# 1-Schematic_Plan_B_elektronisch_schema_o.net
KiCad netlist of a schematic drawn in EasyEDA
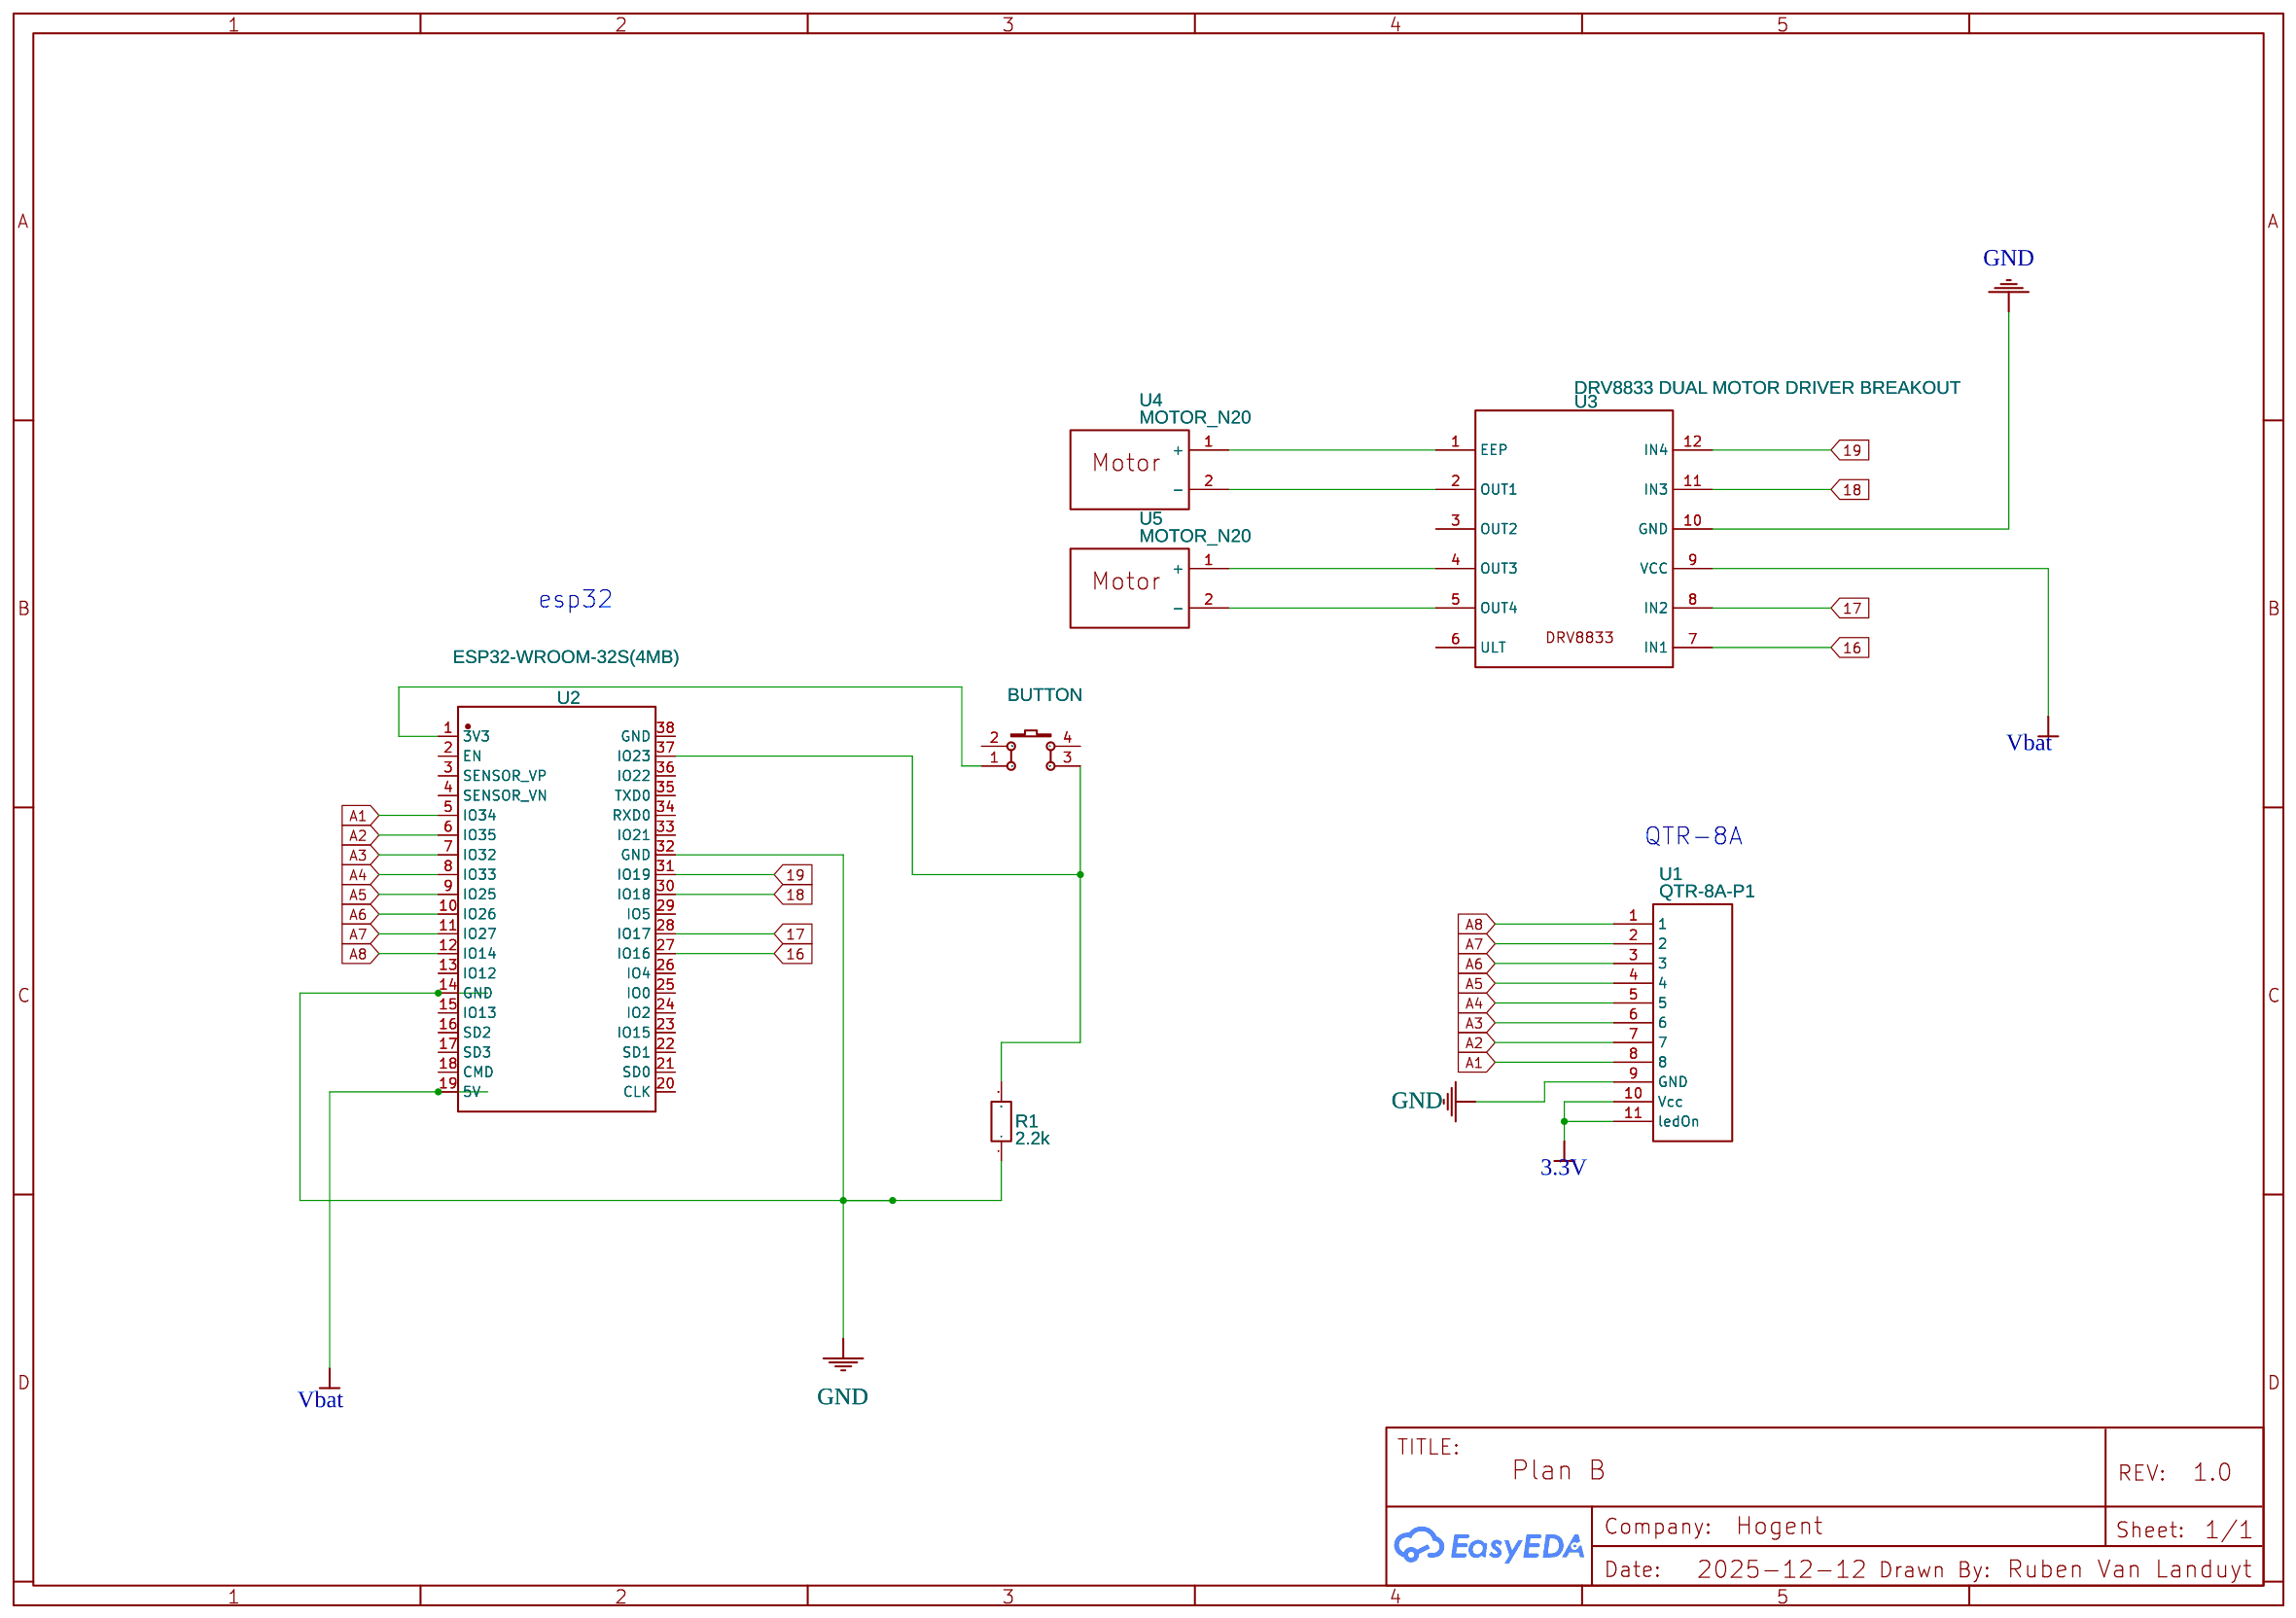
[diagram p0: schematic sheet]

(export (version "E")
  (design (tool "Eeschema 10.0.6"))
  (components
    (comp (ref "BUTTON")
      (value "K4-6×6_SMD")
      (fields (field (name "Manufacturer Part") "K2-6639SP-D4SC-04") (field (name "Manufacturer") "韩国韩荣"))
      (libsource (lib "") (part "K4-6×6_SMD"))
    )
    (comp (ref "R1") (value "2.2k") (libsource (lib "") (part "R_0805_EU")))
    (comp (ref "U1") (value "QTR-8A-P1") (libsource (lib "") (part "QTR-8A-P1")))
    (comp (ref "U2")
      (value "ESP32-WROOM-32S(4MB)")
      (fields (field (name "Manufacturer") "Espressif Systems"))
      (libsource (lib "") (part "ESP32-WROOM-32S(4MB)"))
    )
    (comp (ref "U3")
      (value "DRV8833 DUAL MOTOR DRIVER BREAKOUT")
      (libsource (lib "") (part "DRV8833 DUAL MOTOR DRIVER BREAKOUT"))
    )
    (comp (ref "U4") (value "MOTOR_N20") (libsource (lib "") (part "MOTOR_N20")))
    (comp (ref "U5") (value "MOTOR_N20") (libsource (lib "") (part "MOTOR_N20")))
  )
  (nets
    (net (code "1") (name "3.3V") (class "Default")
      (node (ref "U1") (pin "10") (pinfunction "Vcc_10") (pintype "unspecified"))
      (node (ref "U1") (pin "11") (pinfunction "ledOn_11") (pintype "unspecified"))
    )
    (net (code "2") (name "16") (class "Default")
      (node (ref "U2") (pin "27") (pinfunction "IO16_27") (pintype "unspecified"))
      (node (ref "U3") (pin "7") (pinfunction "IN1_7") (pintype "unspecified"))
    )
    (net (code "3") (name "17") (class "Default")
      (node (ref "U2") (pin "28") (pinfunction "IO17_28") (pintype "unspecified"))
      (node (ref "U3") (pin "8") (pinfunction "IN2_8") (pintype "unspecified"))
    )
    (net (code "4") (name "18") (class "Default")
      (node (ref "U2") (pin "30") (pinfunction "IO18_30") (pintype "unspecified"))
      (node (ref "U3") (pin "11") (pinfunction "IN3_11") (pintype "unspecified"))
    )
    (net (code "5") (name "19") (class "Default")
      (node (ref "U2") (pin "31") (pinfunction "IO19_31") (pintype "unspecified"))
      (node (ref "U3") (pin "12") (pinfunction "IN4_12") (pintype "unspecified"))
    )
    (net (code "6") (name "A1") (class "Default")
      (node (ref "U1") (pin "8") (pinfunction "8_8") (pintype "unspecified"))
      (node (ref "U2") (pin "5") (pinfunction "IO34_5") (pintype "unspecified"))
    )
    (net (code "7") (name "A2") (class "Default")
      (node (ref "U1") (pin "7") (pinfunction "7_7") (pintype "unspecified"))
      (node (ref "U2") (pin "6") (pinfunction "IO35_6") (pintype "unspecified"))
    )
    (net (code "8") (name "A3") (class "Default")
      (node (ref "U1") (pin "6") (pinfunction "6_6") (pintype "unspecified"))
      (node (ref "U2") (pin "7") (pinfunction "IO32_7") (pintype "unspecified"))
    )
    (net (code "9") (name "A4") (class "Default")
      (node (ref "U1") (pin "5") (pinfunction "5_5") (pintype "unspecified"))
      (node (ref "U2") (pin "8") (pinfunction "IO33_8") (pintype "unspecified"))
    )
    (net (code "10") (name "A5") (class "Default")
      (node (ref "U1") (pin "4") (pinfunction "4_4") (pintype "unspecified"))
      (node (ref "U2") (pin "9") (pinfunction "IO25_9") (pintype "unspecified"))
    )
    (net (code "11") (name "A6") (class "Default")
      (node (ref "U1") (pin "3") (pinfunction "3_3") (pintype "unspecified"))
      (node (ref "U2") (pin "10") (pinfunction "IO26_10") (pintype "unspecified"))
    )
    (net (code "12") (name "A7") (class "Default")
      (node (ref "U1") (pin "2") (pinfunction "2_2") (pintype "unspecified"))
      (node (ref "U2") (pin "11") (pinfunction "IO27_11") (pintype "unspecified"))
    )
    (net (code "13") (name "A8") (class "Default")
      (node (ref "U1") (pin "1") (pinfunction "1_1") (pintype "unspecified"))
      (node (ref "U2") (pin "12") (pinfunction "IO14_12") (pintype "unspecified"))
    )
    (net (code "14") (name "GND") (class "Default")
      (node (ref "R1") (pin "1") (pinfunction "1_1") (pintype "unspecified"))
      (node (ref "U1") (pin "9") (pinfunction "GND_9") (pintype "unspecified"))
      (node (ref "U2") (pin "14") (pinfunction "GND_14") (pintype "unspecified"))
      (node (ref "U2") (pin "32") (pinfunction "GND_32") (pintype "unspecified"))
      (node (ref "U3") (pin "10") (pinfunction "GND_10") (pintype "unspecified"))
    )
    (net (code "15") (name "Net-(U2-3V3)") (class "Default")
      (node (ref "BUTTON") (pin "1") (pinfunction "1_1") (pintype "unspecified"))
      (node (ref "U2") (pin "1") (pinfunction "3V3_1") (pintype "unspecified"))
    )
    (net (code "16") (name "Net-(U2-IO23)") (class "Default")
      (node (ref "BUTTON") (pin "3") (pinfunction "3_3") (pintype "unspecified"))
      (node (ref "R1") (pin "2") (pinfunction "2_2") (pintype "unspecified"))
      (node (ref "U2") (pin "37") (pinfunction "IO23_37") (pintype "unspecified"))
    )
    (net (code "17") (name "Net-(U3-EEP)") (class "Default")
      (node (ref "U3") (pin "1") (pinfunction "EEP_1") (pintype "unspecified"))
      (node (ref "U4") (pin "1") (pinfunction "+_1") (pintype "unspecified"))
    )
    (net (code "18") (name "Net-(U3-OUT1)") (class "Default")
      (node (ref "U3") (pin "2") (pinfunction "OUT1_2") (pintype "unspecified"))
      (node (ref "U4") (pin "2") (pinfunction "-_2") (pintype "unspecified"))
    )
    (net (code "19") (name "Net-(U3-OUT3)") (class "Default")
      (node (ref "U3") (pin "4") (pinfunction "OUT3_4") (pintype "unspecified"))
      (node (ref "U5") (pin "1") (pinfunction "+_1") (pintype "unspecified"))
    )
    (net (code "20") (name "Net-(U3-OUT4)") (class "Default")
      (node (ref "U3") (pin "5") (pinfunction "OUT4_5") (pintype "unspecified"))
      (node (ref "U5") (pin "2") (pinfunction "-_2") (pintype "unspecified"))
    )
    (net (code "21") (name "Vbat") (class "Default")
      (node (ref "U2") (pin "19") (pinfunction "5V_19") (pintype "unspecified"))
      (node (ref "U3") (pin "9") (pinfunction "VCC_9") (pintype "unspecified"))
    )
    (net (code "22") (name "unconnected-(BUTTON-Pad2)") (class "Default")
      (node (ref "BUTTON") (pin "2") (pinfunction "2_2") (pintype "unspecified"))
    )
    (net (code "23") (name "unconnected-(BUTTON-Pad4)") (class "Default")
      (node (ref "BUTTON") (pin "4") (pinfunction "4_4") (pintype "unspecified"))
    )
    (net (code "24") (name "unconnected-(U2-CLK-Pad20)") (class "Default")
      (node (ref "U2") (pin "20") (pinfunction "CLK_20") (pintype "unspecified"))
    )
    (net (code "25") (name "unconnected-(U2-CMD-Pad18)") (class "Default")
      (node (ref "U2") (pin "18") (pinfunction "CMD_18") (pintype "unspecified"))
    )
    (net (code "26") (name "unconnected-(U2-EN-Pad2)") (class "Default")
      (node (ref "U2") (pin "2") (pinfunction "EN_2") (pintype "unspecified"))
    )
    (net (code "27") (name "unconnected-(U2-GND-Pad38)") (class "Default")
      (node (ref "U2") (pin "38") (pinfunction "GND_38") (pintype "unspecified"))
    )
    (net (code "28") (name "unconnected-(U2-IO0-Pad25)") (class "Default")
      (node (ref "U2") (pin "25") (pinfunction "IO0_25") (pintype "unspecified"))
    )
    (net (code "29") (name "unconnected-(U2-IO2-Pad24)") (class "Default")
      (node (ref "U2") (pin "24") (pinfunction "IO2_24") (pintype "unspecified"))
    )
    (net (code "30") (name "unconnected-(U2-IO4-Pad26)") (class "Default")
      (node (ref "U2") (pin "26") (pinfunction "IO4_26") (pintype "unspecified"))
    )
    (net (code "31") (name "unconnected-(U2-IO5-Pad29)") (class "Default")
      (node (ref "U2") (pin "29") (pinfunction "IO5_29") (pintype "unspecified"))
    )
    (net (code "32") (name "unconnected-(U2-IO12-Pad13)") (class "Default")
      (node (ref "U2") (pin "13") (pinfunction "IO12_13") (pintype "unspecified"))
    )
    (net (code "33") (name "unconnected-(U2-IO13-Pad15)") (class "Default")
      (node (ref "U2") (pin "15") (pinfunction "IO13_15") (pintype "unspecified"))
    )
    (net (code "34") (name "unconnected-(U2-IO15-Pad23)") (class "Default")
      (node (ref "U2") (pin "23") (pinfunction "IO15_23") (pintype "unspecified"))
    )
    (net (code "35") (name "unconnected-(U2-IO21-Pad33)") (class "Default")
      (node (ref "U2") (pin "33") (pinfunction "IO21_33") (pintype "unspecified"))
    )
    (net (code "36") (name "unconnected-(U2-IO22-Pad36)") (class "Default")
      (node (ref "U2") (pin "36") (pinfunction "IO22_36") (pintype "unspecified"))
    )
    (net (code "37") (name "unconnected-(U2-RXD0-Pad34)") (class "Default")
      (node (ref "U2") (pin "34") (pinfunction "RXD0_34") (pintype "unspecified"))
    )
    (net (code "38") (name "unconnected-(U2-SD0-Pad21)") (class "Default")
      (node (ref "U2") (pin "21") (pinfunction "SD0_21") (pintype "unspecified"))
    )
    (net (code "39") (name "unconnected-(U2-SD1-Pad22)") (class "Default")
      (node (ref "U2") (pin "22") (pinfunction "SD1_22") (pintype "unspecified"))
    )
    (net (code "40") (name "unconnected-(U2-SD2-Pad16)") (class "Default")
      (node (ref "U2") (pin "16") (pinfunction "SD2_16") (pintype "unspecified"))
    )
    (net (code "41") (name "unconnected-(U2-SD3-Pad17)") (class "Default")
      (node (ref "U2") (pin "17") (pinfunction "SD3_17") (pintype "unspecified"))
    )
    (net (code "42") (name "unconnected-(U2-SENSOR_VN-Pad4)") (class "Default")
      (node (ref "U2") (pin "4") (pinfunction "SENSOR_VN_4") (pintype "unspecified"))
    )
    (net (code "43") (name "unconnected-(U2-SENSOR_VP-Pad3)") (class "Default")
      (node (ref "U2") (pin "3") (pinfunction "SENSOR_VP_3") (pintype "unspecified"))
    )
    (net (code "44") (name "unconnected-(U2-TXD0-Pad35)") (class "Default")
      (node (ref "U2") (pin "35") (pinfunction "TXD0_35") (pintype "unspecified"))
    )
    (net (code "45") (name "unconnected-(U3-OUT2-Pad3)") (class "Default")
      (node (ref "U3") (pin "3") (pinfunction "OUT2_3") (pintype "unspecified"))
    )
    (net (code "46") (name "unconnected-(U3-ULT-Pad6)") (class "Default")
      (node (ref "U3") (pin "6") (pinfunction "ULT_6") (pintype "unspecified"))
    )
  )
)
